# Power.net
KiCad netlist of a schematic drawn in Altium Designer
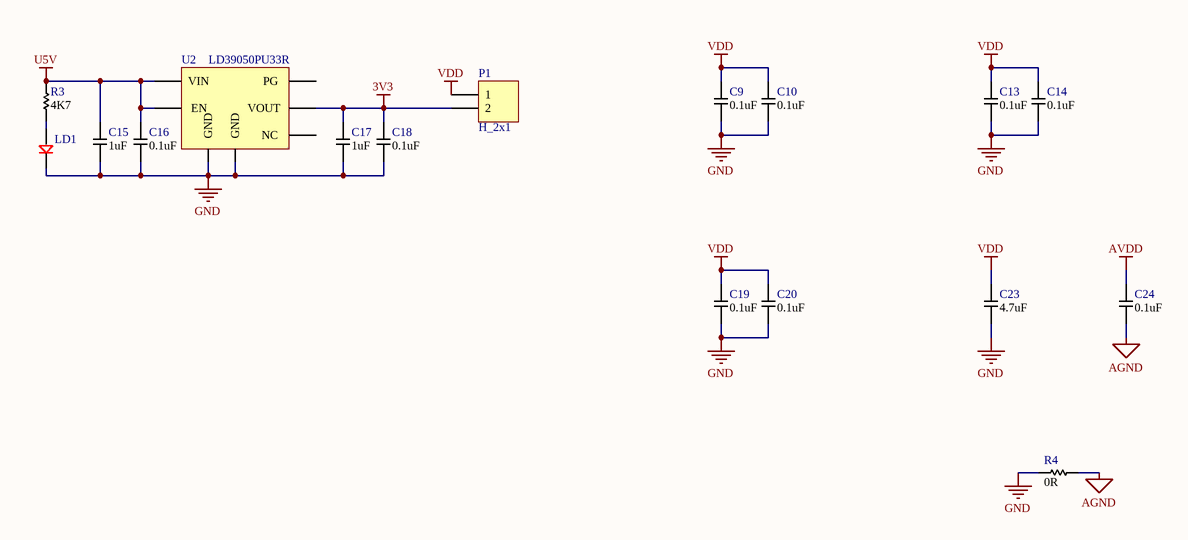
[diagram p0: Power.SchDoc]

(export (version "E")
  (design (tool "Eeschema 10.0.6"))
  (components
    (comp (ref "C9")
      (value "0.1uF")
      (footprint "Kemet_0805_X7R")
      (description "Cap_0805_0.1uF_25VDC_Kemet")
      (fields (field (name "MANUFACTURER") "Kemet") (field (name "VOLTAGE") "25VDC"))
      (libsource (lib "Capacitor") (part "C0805C104K3RACTU"))
    )
    (comp (ref "C10")
      (value "0.1uF")
      (footprint "Kemet_0805_X7R")
      (description "Cap_0805_0.1uF_25VDC_Kemet")
      (fields (field (name "MANUFACTURER") "Kemet") (field (name "VOLTAGE") "25VDC"))
      (libsource (lib "Capacitor") (part "C0805C104K3RACTU"))
    )
    (comp (ref "C13")
      (value "0.1uF")
      (footprint "Kemet_0805_X7R")
      (description "Cap_0805_0.1uF_25VDC_Kemet")
      (fields (field (name "MANUFACTURER") "Kemet") (field (name "VOLTAGE") "25VDC"))
      (libsource (lib "Capacitor") (part "C0805C104K3RACTU"))
    )
    (comp (ref "C14")
      (value "0.1uF")
      (footprint "Kemet_0805_X7R")
      (description "Cap_0805_0.1uF_25VDC_Kemet")
      (fields (field (name "MANUFACTURER") "Kemet") (field (name "VOLTAGE") "25VDC"))
      (libsource (lib "Capacitor") (part "C0805C104K3RACTU"))
    )
    (comp (ref "C15")
      (value "1uF")
      (footprint "Kemet_0805_X7R")
      (description "Cap_0805_1uF_16VDC_Kemet")
      (fields (field (name "MANUFACTURER") "Kemet") (field (name "VOLTAGE") "16VDC"))
      (libsource (lib "Capacitor") (part "C0805C105K4RACTU"))
    )
    (comp (ref "C16")
      (value "0.1uF")
      (footprint "Kemet_0805_X7R")
      (description "Cap_0805_0.1uF_25VDC_Kemet")
      (fields (field (name "MANUFACTURER") "Kemet") (field (name "VOLTAGE") "25VDC"))
      (libsource (lib "Capacitor") (part "C0805C104K3RACTU"))
    )
    (comp (ref "C17")
      (value "1uF")
      (footprint "Kemet_0805_X7R")
      (description "Cap_0805_1uF_16VDC_Kemet")
      (fields (field (name "MANUFACTURER") "Kemet") (field (name "VOLTAGE") "16VDC"))
      (libsource (lib "Capacitor") (part "C0805C105K4RACTU"))
    )
    (comp (ref "C18")
      (value "0.1uF")
      (footprint "Kemet_0805_X7R")
      (description "Cap_0805_0.1uF_25VDC_Kemet")
      (fields (field (name "MANUFACTURER") "Kemet") (field (name "VOLTAGE") "25VDC"))
      (libsource (lib "Capacitor") (part "C0805C104K3RACTU"))
    )
    (comp (ref "C19")
      (value "0.1uF")
      (footprint "Kemet_0805_X7R")
      (description "Cap_0805_0.1uF_25VDC_Kemet")
      (fields (field (name "MANUFACTURER") "Kemet") (field (name "VOLTAGE") "25VDC"))
      (libsource (lib "Capacitor") (part "C0805C104K3RACTU"))
    )
    (comp (ref "C20")
      (value "0.1uF")
      (footprint "Kemet_0805_X7R")
      (description "Cap_0805_0.1uF_25VDC_Kemet")
      (fields (field (name "MANUFACTURER") "Kemet") (field (name "VOLTAGE") "25VDC"))
      (libsource (lib "Capacitor") (part "C0805C104K3RACTU"))
    )
    (comp (ref "C23")
      (value "4.7uF")
      (footprint "Kemet_0805_X7R")
      (description "Cap_0805_0.1uF_25VDC_Kemet")
      (fields (field (name "MANUFACTURER") "Kemet") (field (name "VOLTAGE") "25VDC"))
      (libsource (lib "Capacitor") (part "C0805C104K3RACTU"))
    )
    (comp (ref "C24")
      (value "0.1uF")
      (footprint "Kemet_0805_X7R")
      (description "Cap_0805_0.1uF_25VDC_Kemet")
      (fields (field (name "MANUFACTURER") "Kemet") (field (name "VOLTAGE") "25VDC"))
      (libsource (lib "Capacitor") (part "C0805C104K3RACTU"))
    )
    (comp (ref "LD1")
      (value "17-21/R6C-AP1Q2L/3T")
      (footprint "Everlight_17-21")
      (description "Led_R_1.7V_25mA_Everlight")
      (fields (field (name "MANUFACTURER") "Everlight"))
      (libsource (lib "LED") (part "17-21/R6C-AP1Q2L/3T"))
    )
    (comp (ref "P1")
      (value "H_2x1")
      (footprint "HEADER_HDRV2W65P254_2X1_508X254H945")
      (description "Head_2x1_2.54")
      (libsource (lib "Header") (part "H_2x1"))
    )
    (comp (ref "R3")
      (value "4K7")
      (footprint "VISHAY_RESC205X125X50L35_30N")
      (description "Res_0805_0R_1/8W_Vishay")
      (fields (field (name "MANUFACTURER") "Vishay") (field (name "POWER") "1/8W"))
      (libsource (lib "Resistor") (part "CRCW08050000Z0EA"))
    )
    (comp (ref "R4")
      (value "0R")
      (footprint "VISHAY_RESC205X125X50L35_30N")
      (description "Res_0805_0R_1/8W_Vishay")
      (fields (field (name "MANUFACTURER") "Vishay") (field (name "POWER") "1/8W"))
      (libsource (lib "Resistor") (part "CRCW08050000Z0EA"))
    )
    (comp (ref "U2")
      (value "LD39050PU33R")
      (footprint "TI_SON7P95_300X300X100L40X34T236X162N")
      (description "LinReg_3.3V_500mA_200mV_ST")
      (fields (field (name "MANUFACTURER") "ST"))
      (libsource (lib "LinearRegulator") (part "LD39050PU33R"))
    )
  )
  (nets
    (net (code "1") (name "3V3") (class "Default")
      (node (ref "C17") (pin "2") (pinfunction "2_2") (pintype "passive"))
      (node (ref "C18") (pin "2") (pinfunction "2_2") (pintype "passive"))
      (node (ref "P1") (pin "2") (pinfunction "2_2") (pintype "passive"))
      (node (ref "U2") (pin "4") (pinfunction "VOUT_4") (pintype "passive"))
    )
    (net (code "2") (name "AGND") (class "Default")
      (node (ref "C24") (pin "1") (pinfunction "1_1") (pintype "passive"))
      (node (ref "R4") (pin "1") (pinfunction "1_1") (pintype "passive"))
    )
    (net (code "3") (name "AVDD") (class "Default")
      (node (ref "C24") (pin "2") (pinfunction "2_2") (pintype "passive"))
    )
    (net (code "4") (name "GND") (class "Default")
      (node (ref "C10") (pin "1") (pinfunction "1_1") (pintype "passive"))
      (node (ref "C13") (pin "1") (pinfunction "1_1") (pintype "passive"))
      (node (ref "C14") (pin "1") (pinfunction "1_1") (pintype "passive"))
      (node (ref "C15") (pin "1") (pinfunction "1_1") (pintype "passive"))
      (node (ref "C16") (pin "1") (pinfunction "1_1") (pintype "passive"))
      (node (ref "C17") (pin "1") (pinfunction "1_1") (pintype "passive"))
      (node (ref "C18") (pin "1") (pinfunction "1_1") (pintype "passive"))
      (node (ref "C19") (pin "1") (pinfunction "1_1") (pintype "passive"))
      (node (ref "C20") (pin "1") (pinfunction "1_1") (pintype "passive"))
      (node (ref "C23") (pin "1") (pinfunction "1_1") (pintype "passive"))
      (node (ref "C9") (pin "1") (pinfunction "1_1") (pintype "passive"))
      (node (ref "LD1") (pin "2") (pinfunction "R-_2") (pintype "passive"))
      (node (ref "R4") (pin "2") (pinfunction "2_2") (pintype "passive"))
      (node (ref "U2") (pin "2") (pinfunction "GND_2") (pintype "passive"))
      (node (ref "U2") (pin "7") (pinfunction "GND_7") (pintype "passive"))
    )
    (net (code "5") (name "Net-(LD1-R+)") (class "Default")
      (node (ref "LD1") (pin "1") (pinfunction "R+_1") (pintype "passive"))
      (node (ref "R3") (pin "1") (pinfunction "1_1") (pintype "passive"))
    )
    (net (code "6") (name "U5V") (class "Default")
      (node (ref "C15") (pin "2") (pinfunction "2_2") (pintype "passive"))
      (node (ref "C16") (pin "2") (pinfunction "2_2") (pintype "passive"))
      (node (ref "R3") (pin "2") (pinfunction "2_2") (pintype "passive"))
      (node (ref "U2") (pin "1") (pinfunction "EN_1") (pintype "passive"))
      (node (ref "U2") (pin "6") (pinfunction "VIN_6") (pintype "passive"))
    )
    (net (code "7") (name "VDD") (class "Default")
      (node (ref "C10") (pin "2") (pinfunction "2_2") (pintype "passive"))
      (node (ref "C13") (pin "2") (pinfunction "2_2") (pintype "passive"))
      (node (ref "C14") (pin "2") (pinfunction "2_2") (pintype "passive"))
      (node (ref "C19") (pin "2") (pinfunction "2_2") (pintype "passive"))
      (node (ref "C20") (pin "2") (pinfunction "2_2") (pintype "passive"))
      (node (ref "C23") (pin "2") (pinfunction "2_2") (pintype "passive"))
      (node (ref "C9") (pin "2") (pinfunction "2_2") (pintype "passive"))
      (node (ref "P1") (pin "1") (pinfunction "1_1") (pintype "passive"))
    )
    (net (code "8") (name "unconnected-(U2-NC-Pad5)") (class "Default")
      (node (ref "U2") (pin "5") (pinfunction "NC_5") (pintype "passive"))
    )
    (net (code "9") (name "unconnected-(U2-PG-Pad3)") (class "Default")
      (node (ref "U2") (pin "3") (pinfunction "PG_3") (pintype "passive"))
    )
  )
)
